# Main.net
KiCad netlist of a schematic drawn in Altium Designer
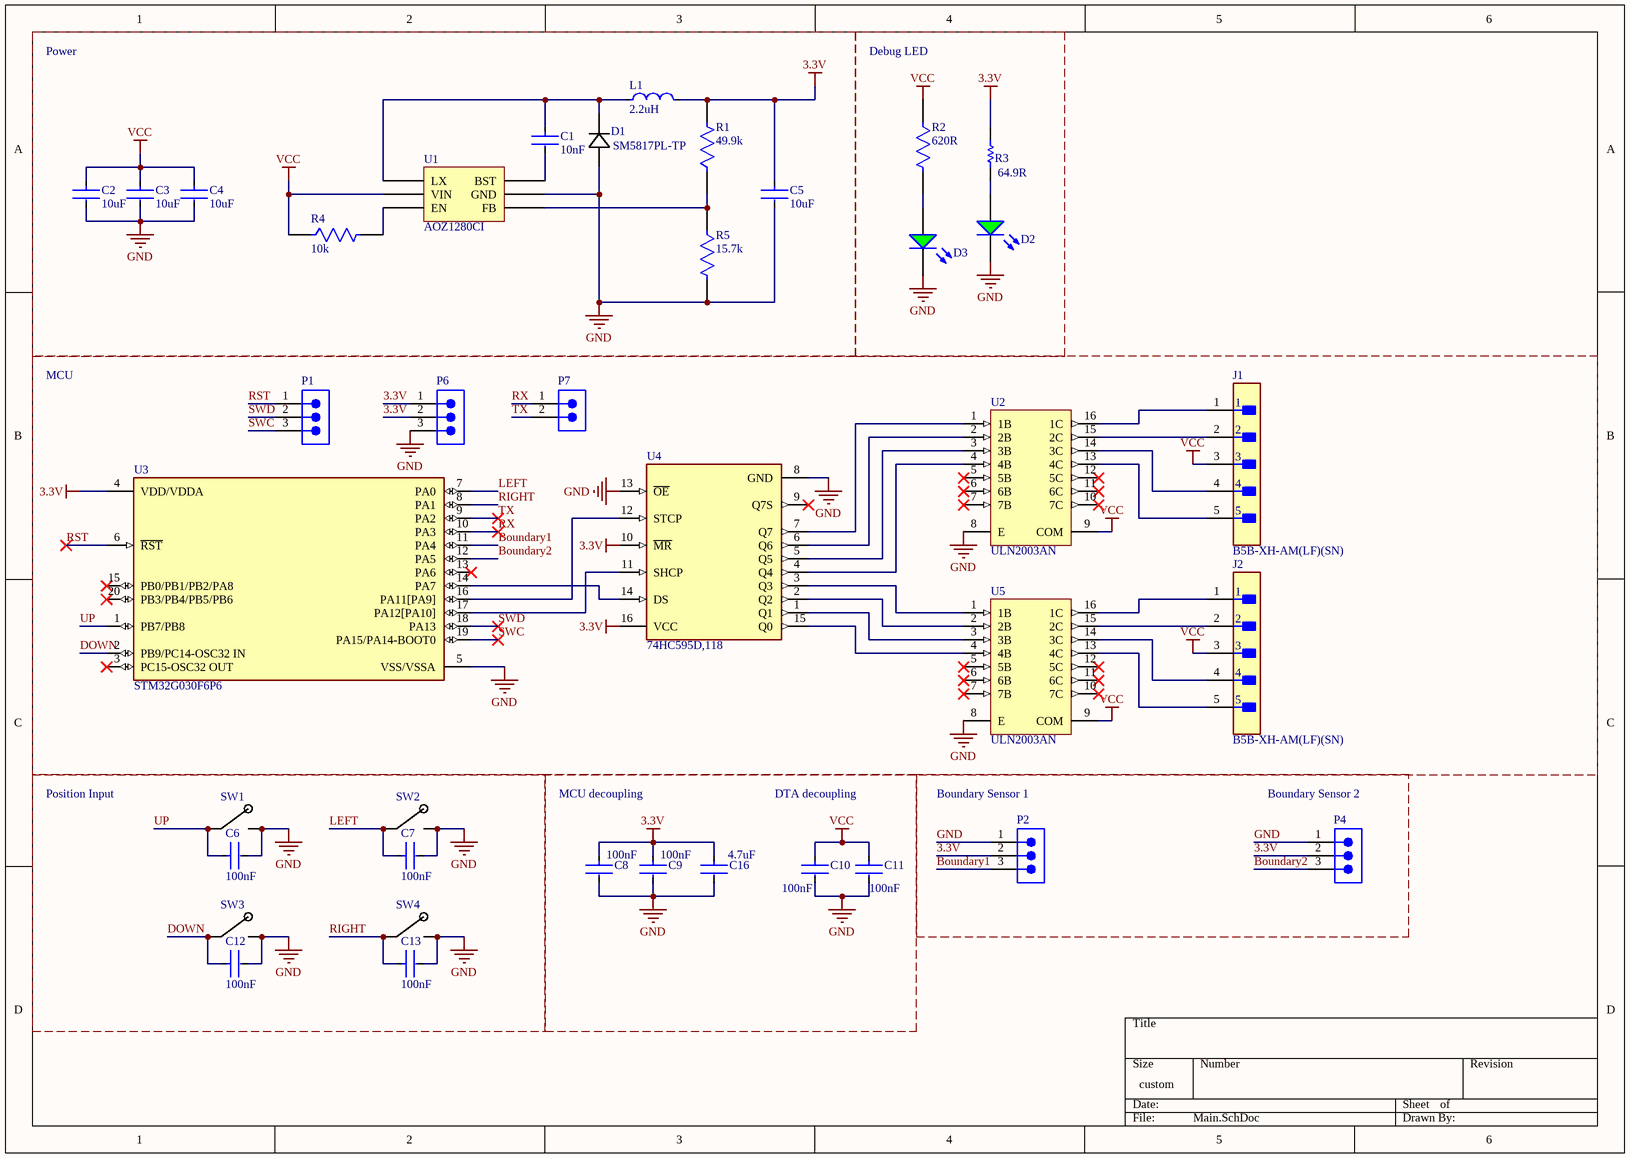
[diagram p0: Main.SchDoc]

(export (version "E")
  (design (tool "Eeschema 10.0.6"))
  (components
    (comp (ref "C1")
      (value "10nF")
      (footprint "FP-CC0603-DA-MFG")
      (description "CAP CER 10000PF 50V X7R 0603")
      (fields (field (name "TOLERANCE") "0.1") (field (name "MANUFACTURER PART NUMBER") "CC0603KRX7R9BB103"))
      (libsource (lib "Altium Content Vault") (part "11868f565c42a9108669ba33697ecf6"))
    )
    (comp (ref "C2")
      (value "10uF")
      (footprint "FP-CL31-IPC_C")
      (description "CAP CER 10UF 50V X5R 1206")
      (fields (field (name "TOLERANCE") "10%") (field (name "MANUFACTURER") "Samsung"))
      (libsource (lib "Altium Content Vault") (part "11868f565c42a9108669ba33697ecf6"))
    )
    (comp (ref "C3")
      (value "10uF")
      (footprint "FP-CL31-IPC_C")
      (description "CAP CER 10UF 50V X5R 1206")
      (fields (field (name "TOLERANCE") "10%") (field (name "MANUFACTURER") "Samsung"))
      (libsource (lib "Altium Content Vault") (part "11868f565c42a9108669ba33697ecf6"))
    )
    (comp (ref "C4")
      (value "10uF")
      (footprint "FP-CL31-IPC_C")
      (description "CAP CER 10UF 50V X5R 1206")
      (fields (field (name "TOLERANCE") "10%") (field (name "MANUFACTURER") "Samsung"))
      (libsource (lib "Altium Content Vault") (part "11868f565c42a9108669ba33697ecf6"))
    )
    (comp (ref "C5")
      (value "10uF")
      (footprint "FP-CL10-IPC_C")
      (description "Cap Ceramic 10uF 6.3V X5R ±20% Pad SMD 0603 +85°C T/R")
      (fields (field (name "VOLTAGE") "6.3V") (field (name "TOLERANCE") "20%"))
      (libsource (lib "Altium Content Vault") (part "b4654b650e69147ec39a6b967a45e02"))
    )
    (comp (ref "C6")
      (value "100nF")
      (footprint "FP-CL10-0_1-MFG")
      (description "CAP CER 0.1UF 50V X7R 0603")
      (fields
        (field (name "MANUFACTURER") "Samsung Electro-Mechanics America, Inc")
        (field (name "MANUFACTURER PART NUMBER") "CL10B104JB8NNNC")
      )
      (libsource (lib "Altium Content Vault") (part "b4654b650e69147ec39a6b967a45e02"))
    )
    (comp (ref "C7")
      (value "100nF")
      (footprint "FP-CL10-0_1-MFG")
      (description "CAP CER 0.1UF 50V X7R 0603")
      (fields
        (field (name "MANUFACTURER") "Samsung Electro-Mechanics America, Inc")
        (field (name "MANUFACTURER PART NUMBER") "CL10B104JB8NNNC")
      )
      (libsource (lib "Altium Content Vault") (part "b4654b650e69147ec39a6b967a45e02"))
    )
    (comp (ref "C8")
      (value "100nF")
      (footprint "FP-CL10-0_1-MFG")
      (description "CAP CER 0.1UF 50V X7R 0603")
      (fields
        (field (name "MANUFACTURER") "Samsung Electro-Mechanics America, Inc")
        (field (name "MANUFACTURER PART NUMBER") "CL10B104JB8NNNC")
      )
      (libsource (lib "Altium Content Vault") (part "b4654b650e69147ec39a6b967a45e02"))
    )
    (comp (ref "C9")
      (value "100nF")
      (footprint "FP-CL10-0_1-MFG")
      (description "CAP CER 0.1UF 50V X7R 0603")
      (fields
        (field (name "MANUFACTURER") "Samsung Electro-Mechanics America, Inc")
        (field (name "MANUFACTURER PART NUMBER") "CL10B104JB8NNNC")
      )
      (libsource (lib "Altium Content Vault") (part "b4654b650e69147ec39a6b967a45e02"))
    )
    (comp (ref "C10")
      (value "100nF")
      (footprint "FP-CL10-0_1-MFG")
      (description "CAP CER 0.1UF 50V X7R 0603")
      (fields
        (field (name "MANUFACTURER") "Samsung Electro-Mechanics America, Inc")
        (field (name "MANUFACTURER PART NUMBER") "CL10B104JB8NNNC")
      )
      (libsource (lib "Altium Content Vault") (part "b4654b650e69147ec39a6b967a45e02"))
    )
    (comp (ref "C11")
      (value "100nF")
      (footprint "FP-CL10-0_1-MFG")
      (description "CAP CER 0.1UF 50V X7R 0603")
      (fields
        (field (name "MANUFACTURER") "Samsung Electro-Mechanics America, Inc")
        (field (name "MANUFACTURER PART NUMBER") "CL10B104JB8NNNC")
      )
      (libsource (lib "Altium Content Vault") (part "b4654b650e69147ec39a6b967a45e02"))
    )
    (comp (ref "C12")
      (value "100nF")
      (footprint "FP-CL10-0_1-MFG")
      (description "CAP CER 0.1UF 50V X7R 0603")
      (fields
        (field (name "MANUFACTURER") "Samsung Electro-Mechanics America, Inc")
        (field (name "MANUFACTURER PART NUMBER") "CL10B104JB8NNNC")
      )
      (libsource (lib "Altium Content Vault") (part "b4654b650e69147ec39a6b967a45e02"))
    )
    (comp (ref "C13")
      (value "100nF")
      (footprint "FP-CL10-0_1-MFG")
      (description "CAP CER 0.1UF 50V X7R 0603")
      (fields
        (field (name "MANUFACTURER") "Samsung Electro-Mechanics America, Inc")
        (field (name "MANUFACTURER PART NUMBER") "CL10B104JB8NNNC")
      )
      (libsource (lib "Altium Content Vault") (part "b4654b650e69147ec39a6b967a45e02"))
    )
    (comp (ref "C16")
      (value "CL10A475KP8NNNC")
      (footprint "FP-CL10-IPC_C")
      (description "Cap Ceramic 4.7uF 10V X5R ±10% Pad SMD 0603 +85°C T/R")
      (fields (field (name "CAPACITANCE") "4.7uF") (field (name "TOLERANCE") "10%"))
      (libsource (lib "Altium Content Vault") (part "b4654b650e69147ec39a6b967a45e02"))
    )
    (comp (ref "D1")
      (value "SM5817PL-TP")
      (footprint "SM5817PL-TP-Footprint-1")
      (description "DIODE SCHOTTKY 20V 1A SOD123FL")
      (libsource (lib "Bento") (part "SM5817PL-TP-Symbol-1"))
    )
    (comp (ref "D2")
      (value "150060VS75000")
      (footprint "WL-SMCW_0603_150060xx75000")
      (libsource (lib "Altium Content Vault") (part "LED_Green_2A-1K"))
    )
    (comp (ref "D3")
      (value "150060VS75000")
      (footprint "WL-SMCW_0603_150060xx75000")
      (libsource (lib "Altium Content Vault") (part "LED_Green_2A-1K"))
    )
    (comp (ref "J1")
      (value "B5B-XH-AM(LF)(SN)")
      (footprint "FP-B5B-XH-AM_LF_SN-MFG")
      (description "CONN HEADER VERT 5POS 2.5MM")
      (libsource (lib "Altium Content Vault") (part "bf93c07fd2649a848d0ec8585582aab"))
    )
    (comp (ref "J2")
      (value "B5B-XH-AM(LF)(SN)")
      (footprint "FP-B5B-XH-AM_LF_SN-MFG")
      (description "CONN HEADER VERT 5POS 2.5MM")
      (libsource (lib "Altium Content Vault") (part "bf93c07fd2649a848d0ec8585582aab"))
    )
    (comp (ref "L1")
      (value "2.2uH")
      (footprint "FP-LQM2MPN_G0-MFG")
      (description "Multilayer Type Inductor for Power Lines, 0806 (2016), 2.2μH, 30%, 0.138Ω, 1.2A")
      (fields (field (name "TOLERANCE") "30%"))
      (libsource (lib "Altium Content Vault") (part "725321dda6339637d4d059423bc1c3c"))
    )
    (comp (ref "P1")
      (value "61300311121")
      (footprint "61300311121")
      (libsource (lib "Altium Content Vault") (part "Header_Male_1R_03P"))
    )
    (comp (ref "P2")
      (value "61300311121")
      (footprint "61300311121")
      (libsource (lib "Altium Content Vault") (part "Header_Male_1R_03P"))
    )
    (comp (ref "P4")
      (value "61300311121")
      (footprint "61300311121")
      (libsource (lib "Altium Content Vault") (part "Header_Male_1R_03P"))
    )
    (comp (ref "P6")
      (value "61300311121")
      (footprint "61300311121")
      (libsource (lib "Altium Content Vault") (part "Header_Male_1R_03P"))
    )
    (comp (ref "P7")
      (value "61300211121")
      (footprint "61300211121")
      (libsource (lib "Altium Content Vault") (part "Header_Male_1R_02P"))
    )
    (comp (ref "R1")
      (value "49.9k")
      (footprint "FP-ERJ3EK-IPC_A")
      (description "RES SMD 49.9K OHM 1% 1/10W 0603")
      (fields (field (name "TOLERANCE") "1%"))
      (libsource (lib "Altium Content Vault") (part "1029c3af85768c4190bb7ad29bc67b5"))
    )
    (comp (ref "R2")
      (value "RMCF0603JT620R")
      (footprint "FP-RMCF0603-MFG")
      (description "620Ω ±5% 0.1W 0603 Thick Film Chip Resistor AEC-Q200 compliant")
      (fields (field (name "RESISTANCE") "620R") (field (name "TOLERANCE") "5%"))
      (libsource (lib "Altium Content Vault") (part "1029c3af85768c4190bb7ad29bc67b5"))
    )
    (comp (ref "R3")
      (value "64.9R")
      (footprint "RESC1608X55X25ML10T15")
      (description "RES 64.9 OHM 1% 1/10W 0603")
      (fields (field (name "MANUFACTURER") "Yageo") (field (name "PART NUMBER") "RC0603FR-0764R9L"))
      (libsource (lib "Altium Content Vault") (part "RES"))
    )
    (comp (ref "R4")
      (value "10k")
      (footprint "FP-RMCF0603-IPC_C")
      (description "10kΩ ±5% 0.1W 0603 Thick Film Chip Resistor AEC-Q200 compliant")
      (fields (field (name "TOLERANCE") "5%"))
      (libsource (lib "Altium Content Vault") (part "1029c3af85768c4190bb7ad29bc67b5"))
    )
    (comp (ref "R5")
      (value "15.7k")
      (footprint "FP-RT0603-MFG")
      (description "RES SMD 15.8K OHM 0.1% 1/10W")
      (fields
        (field (name "OCTOPART") "https://octopart.com/rt0603brd0715k8l-yageo-1418310")
        (field (name "TOLERANCE") "0.001")
      )
      (libsource (lib "Altium Content Vault") (part "1029c3af85768c4190bb7ad29bc67b5"))
    )
    (comp (ref "SW1")
      (value "PTS636 SM43 SMTR LFS")
      (footprint "PTS636 SM43 SMTR LFS-Footprint-1")
      (description "SWITCH TACTILE SPST-NO 0.05A 12V")
      (libsource (lib "Bento") (part "PTS636 SM43 SMTR LFS-Symbol-1"))
    )
    (comp (ref "SW2")
      (value "PTS636 SM43 SMTR LFS")
      (footprint "PTS636 SM43 SMTR LFS-Footprint-1")
      (description "SWITCH TACTILE SPST-NO 0.05A 12V")
      (libsource (lib "Bento") (part "PTS636 SM43 SMTR LFS-Symbol-1"))
    )
    (comp (ref "SW3")
      (value "PTS636 SM43 SMTR LFS")
      (footprint "PTS636 SM43 SMTR LFS-Footprint-1")
      (description "SWITCH TACTILE SPST-NO 0.05A 12V")
      (libsource (lib "Bento") (part "PTS636 SM43 SMTR LFS-Symbol-1"))
    )
    (comp (ref "SW4")
      (value "PTS636 SM43 SMTR LFS")
      (footprint "PTS636 SM43 SMTR LFS-Footprint-1")
      (description "SWITCH TACTILE SPST-NO 0.05A 12V")
      (libsource (lib "Bento") (part "PTS636 SM43 SMTR LFS-Symbol-1"))
    )
    (comp (ref "U1")
      (value "AOZ1280CI")
      (footprint "SOT95P280X125-6N")
      (description "Buck Switching Regulator IC Positive Adjustable 0.8V 1 Output 1.2A SOT-23-6")
      (libsource (lib "Bento") (part "AOZ1280CI-Symbol-1"))
    )
    (comp (ref "U2")
      (value "ULN2003AN")
      (footprint "N0016A")
      (fields (field (name "MANUFACTURER") "TexasInstruments"))
      (libsource (lib "Altium Content Vault") (part "TI-ULN2003A-PDIP_N-16"))
    )
    (comp (ref "U3")
      (value "STM32G030F6P6")
      (footprint "FP-TSSOP20-YA-MFG")
      (description "ARM MICROCONTROLLERS - MCU")
      (fields
        (field (name "MANUFACTURER") "STMicroelectronics")
        (field (name "OCTOPART") "https://octopart.com/stm32g030f6p6-stmicroelectronics-103773023")
      )
      (libsource (lib "Altium Content Vault") (part "de2f7cf56ecdc1f1ec6ab3e49dbf5e6"))
    )
    (comp (ref "U4")
      (value "74HC595D,118")
      (footprint "FP-SOT109-1-IPC_C")
      (description "IC SHIFT REGISTER 8BIT 16SOIC")
      (libsource (lib "Altium Content Vault") (part "7b153f231cfcc3ac06dee253bd56617"))
    )
    (comp (ref "U5")
      (value "ULN2003AN")
      (footprint "N0016A")
      (fields (field (name "MANUFACTURER") "TexasInstruments"))
      (libsource (lib "Altium Content Vault") (part "TI-ULN2003A-PDIP_N-16"))
    )
  )
  (nets
    (net (code "1") (name "/Boundary1") (class "Default")
      (node (ref "P2") (pin "3") (pinfunction "3_3") (pintype "passive"))
      (node (ref "U3") (pin "11") (pinfunction "PA4_11") (pintype "bidirectional"))
    )
    (net (code "2") (name "/Boundary2") (class "Default")
      (node (ref "P4") (pin "3") (pinfunction "3_3") (pintype "passive"))
      (node (ref "U3") (pin "12") (pinfunction "PA5_12") (pintype "bidirectional"))
    )
    (net (code "3") (name "/DOWN") (class "Default")
      (node (ref "C12") (pin "1") (pinfunction "1_1") (pintype "passive"))
      (node (ref "SW3") (pin "1") (pinfunction "1_1") (pintype "passive"))
      (node (ref "U3") (pin "2") (pinfunction "PB9/PC14-OSC32_IN_2") (pintype "bidirectional"))
    )
    (net (code "4") (name "/LEFT") (class "Default")
      (node (ref "C7") (pin "1") (pinfunction "1_1") (pintype "passive"))
      (node (ref "SW2") (pin "1") (pinfunction "1_1") (pintype "passive"))
      (node (ref "U3") (pin "7") (pinfunction "PA0_7") (pintype "bidirectional"))
    )
    (net (code "5") (name "/RIGHT") (class "Default")
      (node (ref "C13") (pin "1") (pinfunction "1_1") (pintype "passive"))
      (node (ref "SW4") (pin "1") (pinfunction "1_1") (pintype "passive"))
      (node (ref "U3") (pin "8") (pinfunction "PA1_8") (pintype "bidirectional"))
    )
    (net (code "6") (name "/RST") (class "Default")
      (node (ref "P1") (pin "1") (pinfunction "1_1") (pintype "passive"))
      (node (ref "U3") (pin "6") (pinfunction "~{RST}_6") (pintype "input"))
    )
    (net (code "7") (name "/RX") (class "Default")
      (node (ref "P7") (pin "1") (pinfunction "1_1") (pintype "passive"))
      (node (ref "U3") (pin "10") (pinfunction "PA3_10") (pintype "bidirectional"))
    )
    (net (code "8") (name "/SWC") (class "Default")
      (node (ref "P1") (pin "3") (pinfunction "3_3") (pintype "passive"))
      (node (ref "U3") (pin "19") (pinfunction "PA15/PA14-BOOT0_19") (pintype "bidirectional"))
    )
    (net (code "9") (name "/SWD") (class "Default")
      (node (ref "P1") (pin "2") (pinfunction "2_2") (pintype "passive"))
      (node (ref "U3") (pin "18") (pinfunction "PA13_18") (pintype "bidirectional"))
    )
    (net (code "10") (name "/TX") (class "Default")
      (node (ref "P7") (pin "2") (pinfunction "2_2") (pintype "passive"))
      (node (ref "U3") (pin "9") (pinfunction "PA2_9") (pintype "bidirectional"))
    )
    (net (code "11") (name "/UP") (class "Default")
      (node (ref "C6") (pin "1") (pinfunction "1_1") (pintype "passive"))
      (node (ref "SW1") (pin "1") (pinfunction "1_1") (pintype "passive"))
      (node (ref "U3") (pin "1") (pinfunction "PB7/PB8_1") (pintype "bidirectional"))
    )
    (net (code "12") (name "3.3V") (class "Default")
      (node (ref "C16") (pin "1") (pinfunction "1_1") (pintype "passive"))
      (node (ref "C5") (pin "1") (pinfunction "1_1") (pintype "passive"))
      (node (ref "C8") (pin "1") (pinfunction "1_1") (pintype "passive"))
      (node (ref "C9") (pin "1") (pinfunction "1_1") (pintype "passive"))
      (node (ref "L1") (pin "2") (pinfunction "2_2") (pintype "passive"))
      (node (ref "P2") (pin "2") (pinfunction "2_2") (pintype "passive"))
      (node (ref "P4") (pin "2") (pinfunction "2_2") (pintype "passive"))
      (node (ref "P6") (pin "1") (pinfunction "1_1") (pintype "passive"))
      (node (ref "P6") (pin "2") (pinfunction "2_2") (pintype "passive"))
      (node (ref "R1") (pin "2") (pinfunction "2_2") (pintype "passive"))
      (node (ref "R3") (pin "2") (pinfunction "2_2") (pintype "passive"))
      (node (ref "U3") (pin "4") (pinfunction "VDD/VDDA_4") (pintype "power_in"))
      (node (ref "U4") (pin "10") (pinfunction "~{MR}_10") (pintype "input"))
      (node (ref "U4") (pin "16") (pinfunction "VCC_16") (pintype "power_in"))
    )
    (net (code "13") (name "GND") (class "Default")
      (node (ref "C10") (pin "2") (pinfunction "2_2") (pintype "passive"))
      (node (ref "C11") (pin "2") (pinfunction "2_2") (pintype "passive"))
      (node (ref "C12") (pin "2") (pinfunction "2_2") (pintype "passive"))
      (node (ref "C13") (pin "2") (pinfunction "2_2") (pintype "passive"))
      (node (ref "C16") (pin "2") (pinfunction "2_2") (pintype "passive"))
      (node (ref "C2") (pin "2") (pinfunction "2_2") (pintype "passive"))
      (node (ref "C3") (pin "2") (pinfunction "2_2") (pintype "passive"))
      (node (ref "C4") (pin "2") (pinfunction "2_2") (pintype "passive"))
      (node (ref "C5") (pin "2") (pinfunction "2_2") (pintype "passive"))
      (node (ref "C6") (pin "2") (pinfunction "2_2") (pintype "passive"))
      (node (ref "C7") (pin "2") (pinfunction "2_2") (pintype "passive"))
      (node (ref "C8") (pin "2") (pinfunction "2_2") (pintype "passive"))
      (node (ref "C9") (pin "2") (pinfunction "2_2") (pintype "passive"))
      (node (ref "D1") (pin "2") (pinfunction "2_2") (pintype "passive"))
      (node (ref "D2") (pin "1") (pinfunction "K_1") (pintype "passive"))
      (node (ref "D3") (pin "1") (pinfunction "K_1") (pintype "passive"))
      (node (ref "P2") (pin "1") (pinfunction "1_1") (pintype "passive"))
      (node (ref "P4") (pin "1") (pinfunction "1_1") (pintype "passive"))
      (node (ref "P6") (pin "3") (pinfunction "3_3") (pintype "passive"))
      (node (ref "R5") (pin "2") (pinfunction "2_2") (pintype "passive"))
      (node (ref "SW1") (pin "2") (pinfunction "2_2") (pintype "passive"))
      (node (ref "SW2") (pin "2") (pinfunction "2_2") (pintype "passive"))
      (node (ref "SW3") (pin "2") (pinfunction "2_2") (pintype "passive"))
      (node (ref "SW4") (pin "2") (pinfunction "2_2") (pintype "passive"))
      (node (ref "U1") (pin "2") (pinfunction "GND_2") (pintype "passive"))
      (node (ref "U2") (pin "8") (pinfunction "E_8") (pintype "passive"))
      (node (ref "U3") (pin "5") (pinfunction "VSS/VSSA_5") (pintype "power_in"))
      (node (ref "U4") (pin "13") (pinfunction "~{OE}_13") (pintype "input"))
      (node (ref "U4") (pin "8") (pinfunction "GND_8") (pintype "power_in"))
      (node (ref "U5") (pin "8") (pinfunction "E_8") (pintype "passive"))
    )
    (net (code "14") (name "Net-(D2-A)") (class "Default")
      (node (ref "D2") (pin "2") (pinfunction "A_2") (pintype "passive"))
      (node (ref "R3") (pin "1") (pinfunction "1_1") (pintype "passive"))
    )
    (net (code "15") (name "Net-(D3-A)") (class "Default")
      (node (ref "D3") (pin "2") (pinfunction "A_2") (pintype "passive"))
      (node (ref "R2") (pin "2") (pinfunction "2_2") (pintype "passive"))
    )
    (net (code "16") (name "Net-(U1-BST)") (class "Default")
      (node (ref "C1") (pin "2") (pinfunction "2_2") (pintype "passive"))
      (node (ref "U1") (pin "1") (pinfunction "BST_1") (pintype "passive"))
    )
    (net (code "17") (name "Net-(U1-EN)") (class "Default")
      (node (ref "R4") (pin "2") (pinfunction "2_2") (pintype "passive"))
      (node (ref "U1") (pin "4") (pinfunction "EN_4") (pintype "passive"))
    )
    (net (code "18") (name "Net-(U1-FB)") (class "Default")
      (node (ref "R1") (pin "1") (pinfunction "1_1") (pintype "passive"))
      (node (ref "R5") (pin "1") (pinfunction "1_1") (pintype "passive"))
      (node (ref "U1") (pin "3") (pinfunction "FB_3") (pintype "passive"))
    )
    (net (code "19") (name "Net-(U1-LX)") (class "Default")
      (node (ref "C1") (pin "1") (pinfunction "1_1") (pintype "passive"))
      (node (ref "D1") (pin "1") (pinfunction "1_1") (pintype "passive"))
      (node (ref "L1") (pin "1") (pinfunction "1_1") (pintype "passive"))
      (node (ref "U1") (pin "6") (pinfunction "LX_6") (pintype "passive"))
    )
    (net (code "20") (name "Net-(U2-1B)") (class "Default")
      (node (ref "U2") (pin "1") (pinfunction "1B_1") (pintype "input"))
      (node (ref "U4") (pin "7") (pinfunction "Q7_7") (pintype "output"))
    )
    (net (code "21") (name "Net-(U2-1C)") (class "Default")
      (node (ref "J1") (pin "1") (pinfunction "1_1") (pintype "passive"))
      (node (ref "U2") (pin "16") (pinfunction "1C_16") (pintype "output"))
    )
    (net (code "22") (name "Net-(U2-2B)") (class "Default")
      (node (ref "U2") (pin "2") (pinfunction "2B_2") (pintype "input"))
      (node (ref "U4") (pin "6") (pinfunction "Q6_6") (pintype "output"))
    )
    (net (code "23") (name "Net-(U2-2C)") (class "Default")
      (node (ref "J1") (pin "2") (pinfunction "2_2") (pintype "passive"))
      (node (ref "U2") (pin "15") (pinfunction "2C_15") (pintype "output"))
    )
    (net (code "24") (name "Net-(U2-3B)") (class "Default")
      (node (ref "U2") (pin "3") (pinfunction "3B_3") (pintype "input"))
      (node (ref "U4") (pin "5") (pinfunction "Q5_5") (pintype "output"))
    )
    (net (code "25") (name "Net-(U2-3C)") (class "Default")
      (node (ref "J1") (pin "4") (pinfunction "4_4") (pintype "passive"))
      (node (ref "U2") (pin "14") (pinfunction "3C_14") (pintype "output"))
    )
    (net (code "26") (name "Net-(U2-4B)") (class "Default")
      (node (ref "U2") (pin "4") (pinfunction "4B_4") (pintype "input"))
      (node (ref "U4") (pin "4") (pinfunction "Q4_4") (pintype "output"))
    )
    (net (code "27") (name "Net-(U2-4C)") (class "Default")
      (node (ref "J1") (pin "5") (pinfunction "5_5") (pintype "passive"))
      (node (ref "U2") (pin "13") (pinfunction "4C_13") (pintype "output"))
    )
    (net (code "28") (name "Net-(U3-PA7)") (class "Default")
      (node (ref "U3") (pin "14") (pinfunction "PA7_14") (pintype "bidirectional"))
      (node (ref "U4") (pin "14") (pinfunction "DS_14") (pintype "input"))
    )
    (net (code "29") (name "Net-(U3-PA11[PA9])") (class "Default")
      (node (ref "U3") (pin "16") (pinfunction "PA11[PA9]_16") (pintype "bidirectional"))
      (node (ref "U4") (pin "12") (pinfunction "STCP_12") (pintype "input"))
    )
    (net (code "30") (name "Net-(U3-PA12[PA10])") (class "Default")
      (node (ref "U3") (pin "17") (pinfunction "PA12[PA10]_17") (pintype "bidirectional"))
      (node (ref "U4") (pin "11") (pinfunction "SHCP_11") (pintype "input"))
    )
    (net (code "31") (name "Net-(U4-Q0)") (class "Default")
      (node (ref "U4") (pin "15") (pinfunction "Q0_15") (pintype "output"))
      (node (ref "U5") (pin "4") (pinfunction "4B_4") (pintype "input"))
    )
    (net (code "32") (name "Net-(U4-Q1)") (class "Default")
      (node (ref "U4") (pin "1") (pinfunction "Q1_1") (pintype "output"))
      (node (ref "U5") (pin "3") (pinfunction "3B_3") (pintype "input"))
    )
    (net (code "33") (name "Net-(U4-Q2)") (class "Default")
      (node (ref "U4") (pin "2") (pinfunction "Q2_2") (pintype "output"))
      (node (ref "U5") (pin "2") (pinfunction "2B_2") (pintype "input"))
    )
    (net (code "34") (name "Net-(U4-Q3)") (class "Default")
      (node (ref "U4") (pin "3") (pinfunction "Q3_3") (pintype "output"))
      (node (ref "U5") (pin "1") (pinfunction "1B_1") (pintype "input"))
    )
    (net (code "35") (name "Net-(U5-1C)") (class "Default")
      (node (ref "J2") (pin "1") (pinfunction "1_1") (pintype "passive"))
      (node (ref "U5") (pin "16") (pinfunction "1C_16") (pintype "output"))
    )
    (net (code "36") (name "Net-(U5-2C)") (class "Default")
      (node (ref "J2") (pin "2") (pinfunction "2_2") (pintype "passive"))
      (node (ref "U5") (pin "15") (pinfunction "2C_15") (pintype "output"))
    )
    (net (code "37") (name "Net-(U5-3C)") (class "Default")
      (node (ref "J2") (pin "4") (pinfunction "4_4") (pintype "passive"))
      (node (ref "U5") (pin "14") (pinfunction "3C_14") (pintype "output"))
    )
    (net (code "38") (name "Net-(U5-4C)") (class "Default")
      (node (ref "J2") (pin "5") (pinfunction "5_5") (pintype "passive"))
      (node (ref "U5") (pin "13") (pinfunction "4C_13") (pintype "output"))
    )
    (net (code "39") (name "VCC") (class "Default")
      (node (ref "C10") (pin "1") (pinfunction "1_1") (pintype "passive"))
      (node (ref "C11") (pin "1") (pinfunction "1_1") (pintype "passive"))
      (node (ref "C2") (pin "1") (pinfunction "1_1") (pintype "passive"))
      (node (ref "C3") (pin "1") (pinfunction "1_1") (pintype "passive"))
      (node (ref "C4") (pin "1") (pinfunction "1_1") (pintype "passive"))
      (node (ref "J1") (pin "3") (pinfunction "3_3") (pintype "passive"))
      (node (ref "J2") (pin "3") (pinfunction "3_3") (pintype "passive"))
      (node (ref "R2") (pin "1") (pinfunction "1_1") (pintype "passive"))
      (node (ref "R4") (pin "1") (pinfunction "1_1") (pintype "passive"))
      (node (ref "U1") (pin "5") (pinfunction "VIN_5") (pintype "power_in"))
      (node (ref "U2") (pin "9") (pinfunction "COM_9") (pintype "passive"))
      (node (ref "U5") (pin "9") (pinfunction "COM_9") (pintype "passive"))
    )
    (net (code "40") (name "unconnected-(U2-5B-Pad5)") (class "Default")
      (node (ref "U2") (pin "5") (pinfunction "5B_5") (pintype "input+no_connect"))
    )
    (net (code "41") (name "unconnected-(U2-5C-Pad12)") (class "Default")
      (node (ref "U2") (pin "12") (pinfunction "5C_12") (pintype "output+no_connect"))
    )
    (net (code "42") (name "unconnected-(U2-6B-Pad6)") (class "Default")
      (node (ref "U2") (pin "6") (pinfunction "6B_6") (pintype "input+no_connect"))
    )
    (net (code "43") (name "unconnected-(U2-6C-Pad11)") (class "Default")
      (node (ref "U2") (pin "11") (pinfunction "6C_11") (pintype "output+no_connect"))
    )
    (net (code "44") (name "unconnected-(U2-7B-Pad7)") (class "Default")
      (node (ref "U2") (pin "7") (pinfunction "7B_7") (pintype "input+no_connect"))
    )
    (net (code "45") (name "unconnected-(U2-7C-Pad10)") (class "Default")
      (node (ref "U2") (pin "10") (pinfunction "7C_10") (pintype "output+no_connect"))
    )
    (net (code "46") (name "unconnected-(U3-PA6-Pad13)") (class "Default")
      (node (ref "U3") (pin "13") (pinfunction "PA6_13") (pintype "bidirectional+no_connect"))
    )
    (net (code "47") (name "unconnected-(U3-PB0{slash}PB1{slash}PB2{slash}PA8-Pad15)") (class "Default")
      (node (ref "U3") (pin "15") (pinfunction "PB0/PB1/PB2/PA8_15") (pintype "bidirectional+no_connect"))
    )
    (net (code "48") (name "unconnected-(U3-PB3{slash}PB4{slash}PB5{slash}PB6-Pad20)") (class "Default")
      (node (ref "U3") (pin "20") (pinfunction "PB3/PB4/PB5/PB6_20") (pintype "bidirectional+no_connect"))
    )
    (net (code "49") (name "unconnected-(U3-PC15-OSC32_OUT-Pad3)") (class "Default")
      (node (ref "U3") (pin "3") (pinfunction "PC15-OSC32_OUT_3") (pintype "bidirectional+no_connect"))
    )
    (net (code "50") (name "unconnected-(U4-Q7S-Pad9)") (class "Default")
      (node (ref "U4") (pin "9") (pinfunction "Q7S_9") (pintype "output+no_connect"))
    )
    (net (code "51") (name "unconnected-(U5-5B-Pad5)") (class "Default")
      (node (ref "U5") (pin "5") (pinfunction "5B_5") (pintype "input+no_connect"))
    )
    (net (code "52") (name "unconnected-(U5-5C-Pad12)") (class "Default")
      (node (ref "U5") (pin "12") (pinfunction "5C_12") (pintype "output+no_connect"))
    )
    (net (code "53") (name "unconnected-(U5-6B-Pad6)") (class "Default")
      (node (ref "U5") (pin "6") (pinfunction "6B_6") (pintype "input+no_connect"))
    )
    (net (code "54") (name "unconnected-(U5-6C-Pad11)") (class "Default")
      (node (ref "U5") (pin "11") (pinfunction "6C_11") (pintype "output+no_connect"))
    )
    (net (code "55") (name "unconnected-(U5-7B-Pad7)") (class "Default")
      (node (ref "U5") (pin "7") (pinfunction "7B_7") (pintype "input+no_connect"))
    )
    (net (code "56") (name "unconnected-(U5-7C-Pad10)") (class "Default")
      (node (ref "U5") (pin "10") (pinfunction "7C_10") (pintype "output+no_connect"))
    )
  )
)
